# TDA-antenna_rev2.net
KiCad netlist of a schematic drawn in Altium Designer
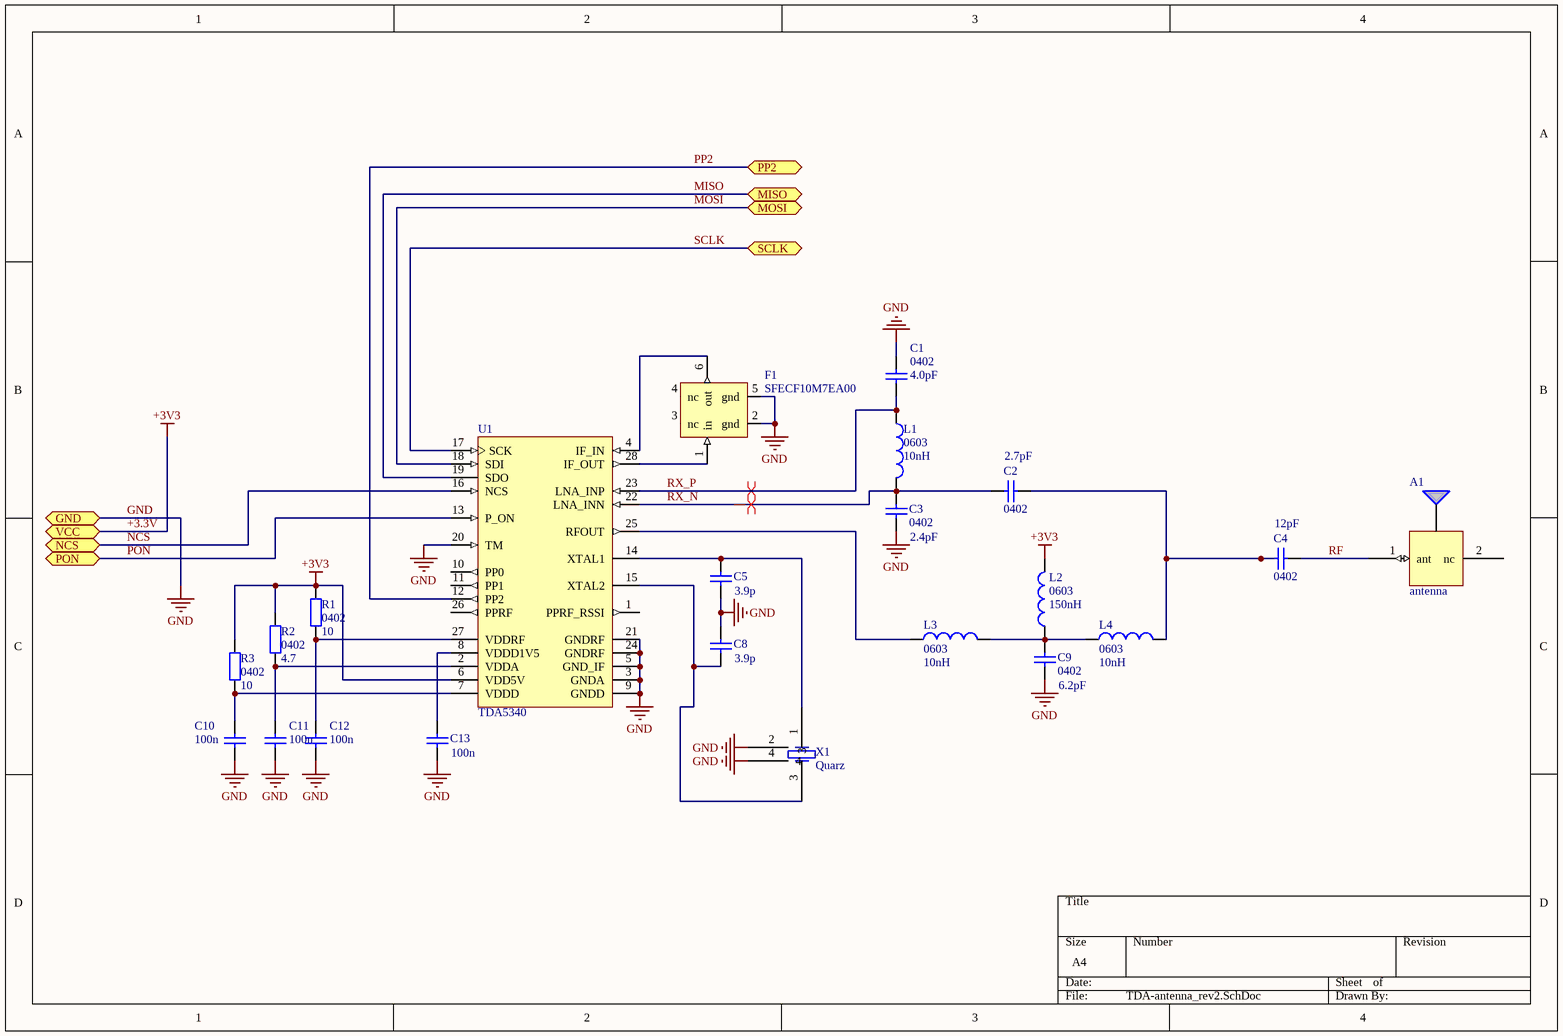
[diagram p0: TDA-antenna_rev2.SchDoc]

(export (version "E")
  (design (tool "Eeschema 10.0.6"))
  (components
    (comp (ref "A1")
      (value "antenna")
      (footprint "Chip Antenna")
      (libsource (lib "Schlib1") (part "antenna"))
    )
    (comp (ref "C1")
      (value "0402")
      (footprint "C0402_M")
      (description "Capacitor")
      (fields (field (name "PART NUMBER") "Cap0402") (field (name "ALTIUM_VALUE") "4.0pF"))
      (libsource (lib "LTE") (part "Cap"))
    )
    (comp (ref "C2")
      (value "0402")
      (footprint "C0402_M")
      (description "Capacitor")
      (fields (field (name "PART NUMBER") "Cap0402") (field (name "ALTIUM_VALUE") "2.7pF"))
      (libsource (lib "LTE") (part "Cap"))
    )
    (comp (ref "C3")
      (value "0402")
      (footprint "C0402_M")
      (description "Capacitor")
      (fields (field (name "PART NUMBER") "Cap0402") (field (name "ALTIUM_VALUE") "2.4pF"))
      (libsource (lib "LTE") (part "Cap"))
    )
    (comp (ref "C4")
      (value "0402")
      (footprint "C0402_M")
      (description "Capacitor")
      (fields (field (name "PART NUMBER") "Cap0402") (field (name "ALTIUM_VALUE") "12pF"))
      (libsource (lib "LTE") (part "Cap"))
    )
    (comp (ref "C5")
      (value "3.9p")
      (footprint "C0402_M")
      (description "Capacitor")
      (fields (field (name "PART NUMBER") "Cap0402") (field (name "Comment") "0402"))
      (libsource (lib "LTE") (part "Cap"))
    )
    (comp (ref "C8")
      (value "3.9p")
      (footprint "C0402_M")
      (description "Capacitor")
      (fields (field (name "PART NUMBER") "Cap0402") (field (name "Comment") "0402"))
      (libsource (lib "LTE") (part "Cap"))
    )
    (comp (ref "C9")
      (value "0402")
      (footprint "C0402_M")
      (description "Capacitor")
      (fields (field (name "PART NUMBER") "Cap0402") (field (name "ALTIUM_VALUE") "6.2pF"))
      (libsource (lib "LTE") (part "Cap"))
    )
    (comp (ref "C10")
      (value "100n")
      (footprint "C0402_M")
      (description "Capacitor")
      (fields (field (name "PART NUMBER") "Cap0402") (field (name "Comment") "0402"))
      (libsource (lib "LTE") (part "Cap"))
    )
    (comp (ref "C11")
      (value "100n")
      (footprint "C0402_M")
      (description "Capacitor")
      (fields (field (name "PART NUMBER") "Cap0402") (field (name "Comment") "0402"))
      (libsource (lib "LTE") (part "Cap"))
    )
    (comp (ref "C12")
      (value "100n")
      (footprint "C0402_M")
      (description "Capacitor")
      (fields (field (name "PART NUMBER") "Cap0402") (field (name "Comment") "0402"))
      (libsource (lib "LTE") (part "Cap"))
    )
    (comp (ref "C13")
      (value "100n")
      (footprint "C0402_M")
      (description "Capacitor")
      (fields (field (name "PART NUMBER") "Cap0402") (field (name "Comment") "0402"))
      (libsource (lib "LTE") (part "Cap"))
    )
    (comp (ref "F1")
      (value "SFECF10M7EA00")
      (footprint "SOP6")
      (libsource (lib "Schlib1") (part "SFECF10M7EA00"))
    )
    (comp (ref "L1")
      (value "0603")
      (footprint "L0603_M")
      (description "Inductor")
      (fields (field (name "ALTIUM_VALUE") "10nH") (field (name "PART NUMBER") "Ind0603"))
      (libsource (lib "LTE") (part "Inductor"))
    )
    (comp (ref "L2")
      (value "0603")
      (footprint "L0603_M")
      (description "Inductor")
      (fields (field (name "ALTIUM_VALUE") "150nH") (field (name "PART NUMBER") "Ind0603"))
      (libsource (lib "LTE") (part "Inductor"))
    )
    (comp (ref "L3")
      (value "0603")
      (footprint "L0603_M")
      (description "Inductor")
      (fields (field (name "ALTIUM_VALUE") "10nH") (field (name "PART NUMBER") "Ind0603"))
      (libsource (lib "LTE") (part "Inductor"))
    )
    (comp (ref "L4")
      (value "0603")
      (footprint "L0603_M")
      (description "Inductor")
      (fields (field (name "ALTIUM_VALUE") "10nH") (field (name "PART NUMBER") "Ind0603"))
      (libsource (lib "LTE") (part "Inductor"))
    )
    (comp (ref "R1")
      (value "0402")
      (footprint "R0402_M")
      (description "Resistor")
      (fields (field (name "PART NUMBER") "Res0402") (field (name "ALTIUM_VALUE") "10"))
      (libsource (lib "LTE") (part "Res"))
    )
    (comp (ref "R2")
      (value "0402")
      (footprint "R0402_M")
      (description "Resistor")
      (fields (field (name "PART NUMBER") "Res0402") (field (name "ALTIUM_VALUE") "4.7"))
      (libsource (lib "LTE") (part "Res"))
    )
    (comp (ref "R3")
      (value "0402")
      (footprint "R0402_M")
      (description "Resistor")
      (fields (field (name "PART NUMBER") "Res0402") (field (name "ALTIUM_VALUE") "10"))
      (libsource (lib "") (part "Res_1"))
    )
    (comp (ref "U1")
      (value "TDA5340")
      (footprint "INF-PG-TSSOP-28_L")
      (description "High Sensitivity Multi-Channel Transceiver, -40 to 110 degC, PG-TSSOP-28, Green")
      (fields (field (name "MANUFACTURER") "Infineon"))
      (libsource (lib "Altium Content Vault") (part "INF-TDA5340-28"))
    )
    (comp (ref "X1") (value "Quarz") (footprint "Quarz") (libsource (lib "Schlib1") (part "Quarz")))
  )
  (nets
    (net (code "1") (name "+3V3") (class "Default")
      (node (ref "L2") (pin "2") (pinfunction "2_2") (pintype "passive"))
      (node (ref "R1") (pin "2") (pinfunction "2_2") (pintype "passive"))
      (node (ref "R2") (pin "2") (pinfunction "2_2") (pintype "passive"))
      (node (ref "R3") (pin "1") (pinfunction "1_1") (pintype "passive"))
      (node (ref "U1") (pin "6") (pinfunction "VDD5V_6") (pintype "power_in"))
    )
    (net (code "2") (name "/MISO") (class "Default")
      (node (ref "U1") (pin "19") (pinfunction "SDO_19") (pintype "tri_state"))
    )
    (net (code "3") (name "/MOSI") (class "Default")
      (node (ref "U1") (pin "18") (pinfunction "SDI_18") (pintype "input"))
    )
    (net (code "4") (name "/NCS") (class "Default")
      (node (ref "U1") (pin "16") (pinfunction "NCS_16") (pintype "input"))
    )
    (net (code "5") (name "/PON") (class "Default")
      (node (ref "U1") (pin "13") (pinfunction "P_ON_13") (pintype "input"))
    )
    (net (code "6") (name "/PP2") (class "Default")
      (node (ref "U1") (pin "12") (pinfunction "PP2_12") (pintype "output"))
    )
    (net (code "7") (name "/RF") (class "Default")
      (node (ref "A1") (pin "1") (pinfunction "ant_1") (pintype "bidirectional"))
      (node (ref "C4") (pin "2") (pinfunction "2_2") (pintype "passive"))
    )
    (net (code "8") (name "/RX_N") (class "Default")
      (node (ref "C2") (pin "2") (pinfunction "2_2") (pintype "passive"))
      (node (ref "C3") (pin "2") (pinfunction "2_2") (pintype "passive"))
      (node (ref "L1") (pin "2") (pinfunction "2_2") (pintype "passive"))
      (node (ref "U1") (pin "22") (pinfunction "LNA_INN_22") (pintype "input"))
    )
    (net (code "9") (name "/RX_P") (class "Default")
      (node (ref "C1") (pin "1") (pinfunction "1_1") (pintype "passive"))
      (node (ref "L1") (pin "1") (pinfunction "1_1") (pintype "passive"))
      (node (ref "U1") (pin "23") (pinfunction "LNA_INP_23") (pintype "input"))
    )
    (net (code "10") (name "/SCLK") (class "Default")
      (node (ref "U1") (pin "17") (pinfunction "SCK_17") (pintype "input"))
    )
    (net (code "11") (name "GND") (class "Default")
      (node (ref "C1") (pin "2") (pinfunction "2_2") (pintype "passive"))
      (node (ref "C10") (pin "1") (pinfunction "1_1") (pintype "passive"))
      (node (ref "C11") (pin "1") (pinfunction "1_1") (pintype "passive"))
      (node (ref "C12") (pin "1") (pinfunction "1_1") (pintype "passive"))
      (node (ref "C13") (pin "1") (pinfunction "1_1") (pintype "passive"))
      (node (ref "C3") (pin "1") (pinfunction "1_1") (pintype "passive"))
      (node (ref "C5") (pin "1") (pinfunction "1_1") (pintype "passive"))
      (node (ref "C8") (pin "2") (pinfunction "2_2") (pintype "passive"))
      (node (ref "C9") (pin "2") (pinfunction "2_2") (pintype "passive"))
      (node (ref "F1") (pin "2") (pinfunction "gnd_2") (pintype "power_in"))
      (node (ref "F1") (pin "5") (pinfunction "gnd_5") (pintype "passive"))
      (node (ref "U1") (pin "20") (pinfunction "TM_20") (pintype "input"))
      (node (ref "U1") (pin "21") (pinfunction "GNDRF_21") (pintype "power_in"))
      (node (ref "U1") (pin "24") (pinfunction "GNDRF_24") (pintype "power_in"))
      (node (ref "U1") (pin "3") (pinfunction "GNDA_3") (pintype "power_in"))
      (node (ref "U1") (pin "5") (pinfunction "GND_IF_5") (pintype "power_in"))
      (node (ref "U1") (pin "9") (pinfunction "GNDD_9") (pintype "power_in"))
      (node (ref "X1") (pin "2") (pinfunction "2_2") (pintype "passive"))
      (node (ref "X1") (pin "4") (pinfunction "4_4") (pintype "passive"))
    )
    (net (code "12") (name "Net-(C2-Pad1)") (class "Default")
      (node (ref "C2") (pin "1") (pinfunction "1_1") (pintype "passive"))
      (node (ref "C4") (pin "1") (pinfunction "1_1") (pintype "passive"))
      (node (ref "L4") (pin "2") (pinfunction "2_2") (pintype "passive"))
    )
    (net (code "13") (name "Net-(C9-Pad1)") (class "Default")
      (node (ref "C9") (pin "1") (pinfunction "1_1") (pintype "passive"))
      (node (ref "L2") (pin "1") (pinfunction "1_1") (pintype "passive"))
      (node (ref "L3") (pin "2") (pinfunction "2_2") (pintype "passive"))
      (node (ref "L4") (pin "1") (pinfunction "1_1") (pintype "passive"))
    )
    (net (code "14") (name "Net-(F1-in)") (class "Default")
      (node (ref "F1") (pin "1") (pinfunction "in_1") (pintype "input"))
      (node (ref "U1") (pin "28") (pinfunction "IF_OUT_28") (pintype "output"))
    )
    (net (code "15") (name "Net-(F1-out)") (class "Default")
      (node (ref "F1") (pin "6") (pinfunction "out_6") (pintype "output"))
      (node (ref "U1") (pin "4") (pinfunction "IF_IN_4") (pintype "input"))
    )
    (net (code "16") (name "Net-(U1-RFOUT)") (class "Default")
      (node (ref "L3") (pin "1") (pinfunction "1_1") (pintype "passive"))
      (node (ref "U1") (pin "25") (pinfunction "RFOUT_25") (pintype "output"))
    )
    (net (code "17") (name "Net-(U1-VDDA)") (class "Default")
      (node (ref "C11") (pin "2") (pinfunction "2_2") (pintype "passive"))
      (node (ref "R2") (pin "1") (pinfunction "1_1") (pintype "passive"))
      (node (ref "U1") (pin "2") (pinfunction "VDDA_2") (pintype "power_in"))
    )
    (net (code "18") (name "Net-(U1-VDDD)") (class "Default")
      (node (ref "C10") (pin "2") (pinfunction "2_2") (pintype "passive"))
      (node (ref "R3") (pin "2") (pinfunction "2_2") (pintype "passive"))
      (node (ref "U1") (pin "7") (pinfunction "VDDD_7") (pintype "power_in"))
    )
    (net (code "19") (name "Net-(U1-VDDD1V5)") (class "Default")
      (node (ref "C13") (pin "2") (pinfunction "2_2") (pintype "passive"))
      (node (ref "U1") (pin "8") (pinfunction "VDDD1V5_8") (pintype "power_in"))
    )
    (net (code "20") (name "Net-(U1-VDDRF)") (class "Default")
      (node (ref "C12") (pin "2") (pinfunction "2_2") (pintype "passive"))
      (node (ref "R1") (pin "1") (pinfunction "1_1") (pintype "passive"))
      (node (ref "U1") (pin "27") (pinfunction "VDDRF_27") (pintype "power_in"))
    )
    (net (code "21") (name "Net-(U1-XTAL1)") (class "Default")
      (node (ref "C5") (pin "2") (pinfunction "2_2") (pintype "passive"))
      (node (ref "U1") (pin "14") (pinfunction "XTAL1_14") (pintype "passive"))
      (node (ref "X1") (pin "1") (pinfunction "1_1") (pintype "passive"))
    )
    (net (code "22") (name "Net-(U1-XTAL2)") (class "Default")
      (node (ref "C8") (pin "1") (pinfunction "1_1") (pintype "passive"))
      (node (ref "U1") (pin "15") (pinfunction "XTAL2_15") (pintype "passive"))
      (node (ref "X1") (pin "3") (pinfunction "3_3") (pintype "passive"))
    )
    (net (code "23") (name "unconnected-(A1-nc-Pad2)") (class "Default")
      (node (ref "A1") (pin "2") (pinfunction "nc_2") (pintype "passive"))
    )
    (net (code "24") (name "unconnected-(F1-nc-Pad3)") (class "Default")
      (node (ref "F1") (pin "3") (pinfunction "nc_3") (pintype "passive"))
    )
    (net (code "25") (name "unconnected-(F1-nc-Pad4)") (class "Default")
      (node (ref "F1") (pin "4") (pinfunction "nc_4") (pintype "passive"))
    )
    (net (code "26") (name "unconnected-(U1-PP0-Pad10)") (class "Default")
      (node (ref "U1") (pin "10") (pinfunction "PP0_10") (pintype "output"))
    )
    (net (code "27") (name "unconnected-(U1-PP1-Pad11)") (class "Default")
      (node (ref "U1") (pin "11") (pinfunction "PP1_11") (pintype "output"))
    )
    (net (code "28") (name "unconnected-(U1-PPRF-Pad26)") (class "Default")
      (node (ref "U1") (pin "26") (pinfunction "PPRF_26") (pintype "output"))
    )
    (net (code "29") (name "unconnected-(U1-PPRF_RSSI-Pad1)") (class "Default")
      (node (ref "U1") (pin "1") (pinfunction "PPRF_RSSI_1") (pintype "output"))
    )
  )
)
